# pcb_lipo.net
KiCad netlist of a schematic drawn in EAGLE
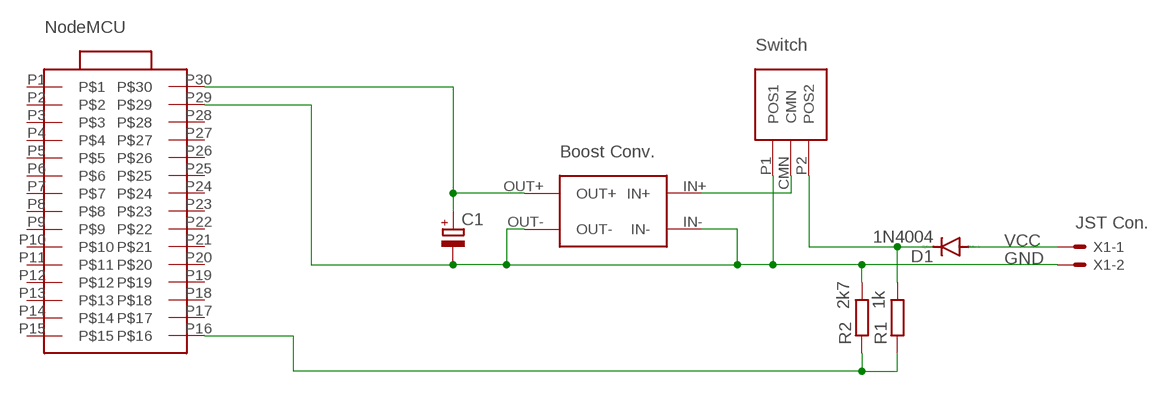
[diagram p0: schematic, sheet 1]

(export (version "E")
  (design (tool "Eeschema 10.0.6"))
  (components
    (comp (ref "C1")
      (value "CPOL-EUE1.8-4")
      (footprint "eagle-import:E1,8-4")
      (libsource (lib "eagle-import") (part "CPOL-EUE1.8-4"))
    )
    (comp (ref "D1")
      (value "1N4004")
      (footprint "eagle-import:DO41-10")
      (libsource (lib "eagle-import") (part "1N4004"))
    )
    (comp (ref "R1")
      (value "1k")
      (footprint "eagle-import:0207_7")
      (libsource (lib "eagle-import") (part "R-EU_0207/7"))
    )
    (comp (ref "R2")
      (value "2k7")
      (footprint "eagle-import:0207_7")
      (libsource (lib "eagle-import") (part "R-EU_0207/7"))
    )
    (comp (ref "U$1")
      (value "NODEMCU")
      (footprint "eagle-import:DIP")
      (libsource (lib "eagle-import") (part "NODEMCU"))
    )
    (comp (ref "U$2")
      (value "MODULE")
      (footprint "eagle-import:MODULE")
      (libsource (lib "eagle-import") (part "MODULE"))
    )
    (comp (ref "U$3")
      (value "SWITCH")
      (footprint "eagle-import:DIP")
      (libsource (lib "eagle-import") (part "SWITCH"))
    )
    (comp (ref "X1")
      (value "22-23-2021")
      (footprint "eagle-import:22-23-2021")
      (fields (field (name "MF") "MOLEX"))
      (libsource (lib "eagle-import") (part "22-23-2021"))
    )
  )
  (nets
    (net (code "1") (name "/GND") (class "Default")
      (node (ref "C1") (pin "-") (pinfunction "-_-") (pintype "passive"))
      (node (ref "R2") (pin "2") (pinfunction "2_2") (pintype "passive"))
      (node (ref "U$1") (pin "P29") (pinfunction "P$29_P29") (pintype "bidirectional"))
      (node (ref "U$2") (pin "IN-") (pinfunction "IN-_IN-") (pintype "bidirectional"))
      (node (ref "U$2") (pin "OUT-") (pinfunction "OUT-_OUT-") (pintype "bidirectional"))
      (node (ref "U$3") (pin "P1") (pinfunction "POS1_P1") (pintype "bidirectional"))
      (node (ref "X1") (pin "2") (pinfunction "S_2") (pintype "passive"))
    )
    (net (code "2") (name "/VCC") (class "Default")
      (node (ref "D1") (pin "A") (pinfunction "A_A") (pintype "passive"))
      (node (ref "X1") (pin "1") (pinfunction "S_1") (pintype "passive"))
    )
    (net (code "3") (name "Net-(U$1-P$16)") (class "Default")
      (node (ref "R1") (pin "1") (pinfunction "1_1") (pintype "passive"))
      (node (ref "R2") (pin "1") (pinfunction "1_1") (pintype "passive"))
      (node (ref "U$1") (pin "P16") (pinfunction "P$16_P16") (pintype "bidirectional"))
    )
    (net (code "4") (name "Net-(U$1-P$30)") (class "Default")
      (node (ref "C1") (pin "+") (pinfunction "+_+") (pintype "passive"))
      (node (ref "U$1") (pin "P30") (pinfunction "P$30_P30") (pintype "bidirectional"))
      (node (ref "U$2") (pin "OUT+") (pinfunction "OUT+_OUT+") (pintype "bidirectional"))
    )
    (net (code "5") (name "Net-(U$2-PadIN+)") (class "Default")
      (node (ref "U$2") (pin "IN+") (pinfunction "IN+_IN+") (pintype "bidirectional"))
      (node (ref "U$3") (pin "CMN") (pinfunction "CMN_CMN") (pintype "bidirectional"))
    )
    (net (code "6") (name "Net-(U$3-POS2)") (class "Default")
      (node (ref "D1") (pin "C") (pinfunction "C_C") (pintype "passive"))
      (node (ref "R1") (pin "2") (pinfunction "2_2") (pintype "passive"))
      (node (ref "U$3") (pin "P2") (pinfunction "POS2_P2") (pintype "bidirectional"))
    )
    (net (code "7") (name "unconnected-(U$1-P$1-PadP1)") (class "Default")
      (node (ref "U$1") (pin "P1") (pinfunction "P$1_P1") (pintype "bidirectional"))
    )
    (net (code "8") (name "unconnected-(U$1-P$2-PadP2)") (class "Default")
      (node (ref "U$1") (pin "P2") (pinfunction "P$2_P2") (pintype "bidirectional"))
    )
    (net (code "9") (name "unconnected-(U$1-P$3-PadP3)") (class "Default")
      (node (ref "U$1") (pin "P3") (pinfunction "P$3_P3") (pintype "bidirectional"))
    )
    (net (code "10") (name "unconnected-(U$1-P$4-PadP4)") (class "Default")
      (node (ref "U$1") (pin "P4") (pinfunction "P$4_P4") (pintype "bidirectional"))
    )
    (net (code "11") (name "unconnected-(U$1-P$5-PadP5)") (class "Default")
      (node (ref "U$1") (pin "P5") (pinfunction "P$5_P5") (pintype "bidirectional"))
    )
    (net (code "12") (name "unconnected-(U$1-P$6-PadP6)") (class "Default")
      (node (ref "U$1") (pin "P6") (pinfunction "P$6_P6") (pintype "bidirectional"))
    )
    (net (code "13") (name "unconnected-(U$1-P$7-PadP7)") (class "Default")
      (node (ref "U$1") (pin "P7") (pinfunction "P$7_P7") (pintype "bidirectional"))
    )
    (net (code "14") (name "unconnected-(U$1-P$8-PadP8)") (class "Default")
      (node (ref "U$1") (pin "P8") (pinfunction "P$8_P8") (pintype "bidirectional"))
    )
    (net (code "15") (name "unconnected-(U$1-P$9-PadP9)") (class "Default")
      (node (ref "U$1") (pin "P9") (pinfunction "P$9_P9") (pintype "bidirectional"))
    )
    (net (code "16") (name "unconnected-(U$1-P$10-PadP10)") (class "Default")
      (node (ref "U$1") (pin "P10") (pinfunction "P$10_P10") (pintype "bidirectional"))
    )
    (net (code "17") (name "unconnected-(U$1-P$11-PadP11)") (class "Default")
      (node (ref "U$1") (pin "P11") (pinfunction "P$11_P11") (pintype "bidirectional"))
    )
    (net (code "18") (name "unconnected-(U$1-P$12-PadP12)") (class "Default")
      (node (ref "U$1") (pin "P12") (pinfunction "P$12_P12") (pintype "bidirectional"))
    )
    (net (code "19") (name "unconnected-(U$1-P$13-PadP13)") (class "Default")
      (node (ref "U$1") (pin "P13") (pinfunction "P$13_P13") (pintype "bidirectional"))
    )
    (net (code "20") (name "unconnected-(U$1-P$14-PadP14)") (class "Default")
      (node (ref "U$1") (pin "P14") (pinfunction "P$14_P14") (pintype "bidirectional"))
    )
    (net (code "21") (name "unconnected-(U$1-P$15-PadP15)") (class "Default")
      (node (ref "U$1") (pin "P15") (pinfunction "P$15_P15") (pintype "bidirectional"))
    )
    (net (code "22") (name "unconnected-(U$1-P$17-PadP17)") (class "Default")
      (node (ref "U$1") (pin "P17") (pinfunction "P$17_P17") (pintype "bidirectional"))
    )
    (net (code "23") (name "unconnected-(U$1-P$18-PadP18)") (class "Default")
      (node (ref "U$1") (pin "P18") (pinfunction "P$18_P18") (pintype "bidirectional"))
    )
    (net (code "24") (name "unconnected-(U$1-P$19-PadP19)") (class "Default")
      (node (ref "U$1") (pin "P19") (pinfunction "P$19_P19") (pintype "bidirectional"))
    )
    (net (code "25") (name "unconnected-(U$1-P$20-PadP20)") (class "Default")
      (node (ref "U$1") (pin "P20") (pinfunction "P$20_P20") (pintype "bidirectional"))
    )
    (net (code "26") (name "unconnected-(U$1-P$21-PadP21)") (class "Default")
      (node (ref "U$1") (pin "P21") (pinfunction "P$21_P21") (pintype "bidirectional"))
    )
    (net (code "27") (name "unconnected-(U$1-P$22-PadP22)") (class "Default")
      (node (ref "U$1") (pin "P22") (pinfunction "P$22_P22") (pintype "bidirectional"))
    )
    (net (code "28") (name "unconnected-(U$1-P$23-PadP23)") (class "Default")
      (node (ref "U$1") (pin "P23") (pinfunction "P$23_P23") (pintype "bidirectional"))
    )
    (net (code "29") (name "unconnected-(U$1-P$24-PadP24)") (class "Default")
      (node (ref "U$1") (pin "P24") (pinfunction "P$24_P24") (pintype "bidirectional"))
    )
    (net (code "30") (name "unconnected-(U$1-P$25-PadP25)") (class "Default")
      (node (ref "U$1") (pin "P25") (pinfunction "P$25_P25") (pintype "bidirectional"))
    )
    (net (code "31") (name "unconnected-(U$1-P$26-PadP26)") (class "Default")
      (node (ref "U$1") (pin "P26") (pinfunction "P$26_P26") (pintype "bidirectional"))
    )
    (net (code "32") (name "unconnected-(U$1-P$27-PadP27)") (class "Default")
      (node (ref "U$1") (pin "P27") (pinfunction "P$27_P27") (pintype "bidirectional"))
    )
    (net (code "33") (name "unconnected-(U$1-P$28-PadP28)") (class "Default")
      (node (ref "U$1") (pin "P28") (pinfunction "P$28_P28") (pintype "bidirectional"))
    )
  )
)
